# PowerBlock.net
KiCad netlist of a schematic drawn in Altium Designer
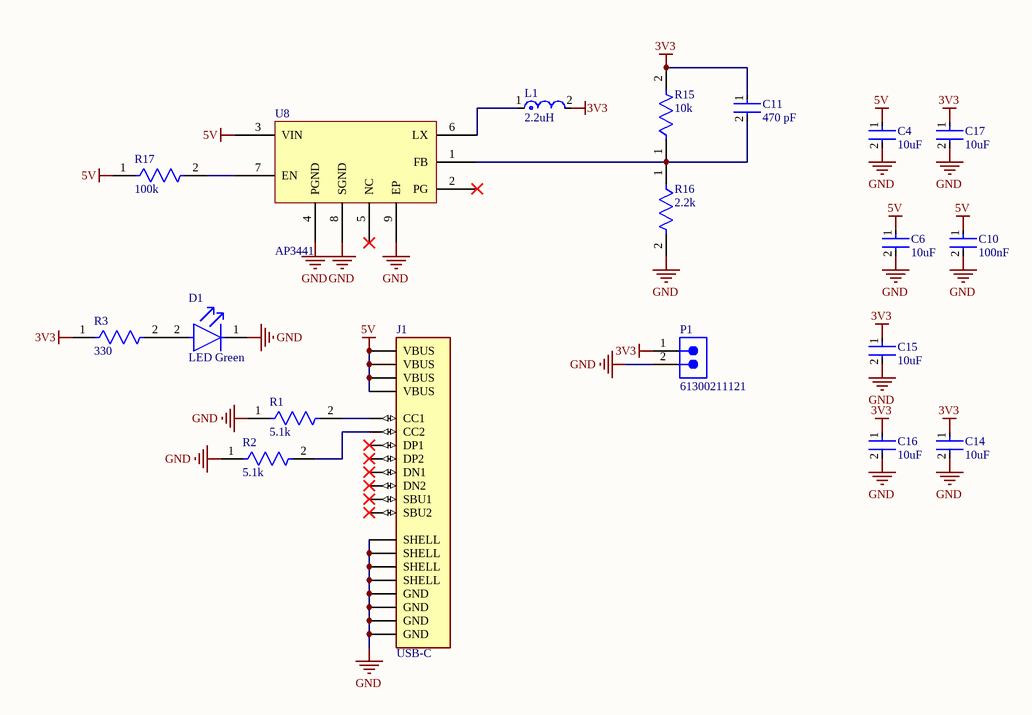
[diagram p0: PowerBlock.SchDoc]

(export (version "E")
  (design (tool "Eeschema 10.0.6"))
  (components
    (comp (ref "C4")
      (value "10uF")
      (footprint "FP-C0805C106K3PACTU-MFG")
      (description "CAP CER 10UF 25V X5R 0805")
      (fields (field (name "TOLERANCE") "10%") (field (name "VOLTAGE") "25V"))
      (libsource (lib "Altium Content Vault") (part "b4654b650e69147ec39a6b967a45e02"))
    )
    (comp (ref "C6")
      (value "10uF")
      (footprint "FP-C0805C106K3PACTU-MFG")
      (description "CAP CER 10UF 25V X5R 0805")
      (fields (field (name "TOLERANCE") "10%") (field (name "VOLTAGE") "25V"))
      (libsource (lib "Altium Content Vault") (part "b4654b650e69147ec39a6b967a45e02"))
    )
    (comp (ref "C10")
      (value "100nF")
      (footprint "FP-C0805C106K3PACTU-MFG")
      (description "CAP CER 10UF 25V X5R 0805")
      (fields (field (name "TOLERANCE") "10%") (field (name "VOLTAGE") "25V"))
      (libsource (lib "Altium Content Vault") (part "b4654b650e69147ec39a6b967a45e02"))
    )
    (comp (ref "C11")
      (value "470 pF")
      (footprint "FP-C0805C106K3PACTU-MFG")
      (description "CAP CER 10UF 25V X5R 0805")
      (fields (field (name "TOLERANCE") "10%") (field (name "VOLTAGE") "25V"))
      (libsource (lib "Altium Content Vault") (part "b4654b650e69147ec39a6b967a45e02"))
    )
    (comp (ref "C14")
      (value "10uF")
      (footprint "FP-C0805C106K3PACTU-MFG")
      (description "CAP CER 10UF 25V X5R 0805")
      (fields (field (name "TOLERANCE") "10%") (field (name "VOLTAGE") "25V"))
      (libsource (lib "Altium Content Vault") (part "b4654b650e69147ec39a6b967a45e02"))
    )
    (comp (ref "C15")
      (value "10uF")
      (footprint "FP-C0805C106K3PACTU-MFG")
      (description "CAP CER 10UF 25V X5R 0805")
      (fields (field (name "TOLERANCE") "10%") (field (name "VOLTAGE") "25V"))
      (libsource (lib "Altium Content Vault") (part "b4654b650e69147ec39a6b967a45e02"))
    )
    (comp (ref "C16")
      (value "10uF")
      (footprint "FP-C0805C106K3PACTU-MFG")
      (description "CAP CER 10UF 25V X5R 0805")
      (fields (field (name "TOLERANCE") "10%") (field (name "VOLTAGE") "25V"))
      (libsource (lib "Altium Content Vault") (part "b4654b650e69147ec39a6b967a45e02"))
    )
    (comp (ref "C17")
      (value "10uF")
      (footprint "FP-C0805C106K3PACTU-MFG")
      (description "CAP CER 10UF 25V X5R 0805")
      (fields (field (name "TOLERANCE") "10%") (field (name "VOLTAGE") "25V"))
      (libsource (lib "Altium Content Vault") (part "b4654b650e69147ec39a6b967a45e02"))
    )
    (comp (ref "D1")
      (value "LED Green")
      (footprint "FP-LTST-C171KGKT-MFG")
      (description "LED GREEN CLEAR SMD")
      (libsource (lib "Altium Content Vault") (part "8706943c75ba83719d021d2fdc84c58"))
    )
    (comp (ref "J1")
      (value "USB-C")
      (footprint "GCT_USB4085-GF-A_REVA4")
      (fields (field (name "MP") "USB4085-GF-A") (field (name "MF") "Global Connector Technology"))
      (libsource (lib "PowerBlock") (part "USB4085-GF-A_REVA4"))
    )
    (comp (ref "L1")
      (value "2.2uH")
      (footprint "FP-XAL4020-MFG")
      (description "Fixed Inductors 2.2uH Shld 20% 5.5A 38.7mOhms AECQ2")
      (fields (field (name "TOLERANCE") "20%"))
      (libsource (lib "Altium Content Vault") (part "4cc4b267dca4c8e51f7102f422741d8"))
    )
    (comp (ref "P1")
      (value "61300211121")
      (footprint "61300211121")
      (description "THT Vertical Pin Header WR-PHD, Pitch 2.54 mm, Single Row, 2 pins")
      (libsource (lib "Altium Content Vault") (part "Header_Male_1R_02P"))
    )
    (comp (ref "R1")
      (value "5.1k")
      (footprint "FP-CRGP0805-IPC_C")
      (description "CRGP 0805 10K 1%")
      (fields (field (name "MANUFACTURER PART NUMBER") "CRGP0805F10K") (field (name "MANUFACTURER") "TE"))
      (libsource (lib "Altium Content Vault") (part "1029c3af85768c4190bb7ad29bc67b5"))
    )
    (comp (ref "R2")
      (value "5.1k")
      (footprint "FP-CRGP0805-IPC_C")
      (description "CRGP 0805 10K 1%")
      (fields (field (name "MANUFACTURER PART NUMBER") "CRGP0805F10K") (field (name "MANUFACTURER") "TE"))
      (libsource (lib "Altium Content Vault") (part "1029c3af85768c4190bb7ad29bc67b5"))
    )
    (comp (ref "R3")
      (value "330")
      (footprint "FP-CRGP0805-IPC_C")
      (description "CRGP 0805 10K 1%")
      (fields (field (name "MANUFACTURER PART NUMBER") "CRGP0805F10K") (field (name "MANUFACTURER") "TE"))
      (libsource (lib "Altium Content Vault") (part "1029c3af85768c4190bb7ad29bc67b5"))
    )
    (comp (ref "R15")
      (value "10k")
      (footprint "FP-CRGP0805-IPC_C")
      (description "CRGP 0805 10K 1%")
      (fields (field (name "MANUFACTURER PART NUMBER") "CRGP0805F10K") (field (name "MANUFACTURER") "TE"))
      (libsource (lib "Altium Content Vault") (part "1029c3af85768c4190bb7ad29bc67b5"))
    )
    (comp (ref "R16")
      (value "2.2k")
      (footprint "FP-CRGP0805-IPC_C")
      (description "CRGP 0805 10K 1%")
      (fields (field (name "MANUFACTURER PART NUMBER") "CRGP0805F10K") (field (name "MANUFACTURER") "TE"))
      (libsource (lib "Altium Content Vault") (part "1029c3af85768c4190bb7ad29bc67b5"))
    )
    (comp (ref "R17")
      (value "100k")
      (footprint "FP-CRGP0805-IPC_C")
      (description "CRGP 0805 10K 1%")
      (fields (field (name "MANUFACTURER PART NUMBER") "CRGP0805F10K") (field (name "MANUFACTURER") "TE"))
      (libsource (lib "Altium Content Vault") (part "1029c3af85768c4190bb7ad29bc67b5"))
    )
    (comp (ref "U8")
      (value "AP3441")
      (footprint "SON50P201X201X60-9M")
      (description "DC-DC Switching Buck Regulator, Adjustable, 2.7 to 5.5 V in, 0.6 to 5.5 V/3 A, U-DFN2020-8")
      (fields
        (field (name "MANUFACTURER") "Diodes Inc.")
        (field (name "MANUFACTURER PART NUMBER") "AP3441LSHE-7B")
      )
      (libsource (lib "PowerBlock") (part "AP3441LSHE-7B"))
    )
  )
  (nets
    (net (code "1") (name "3V3") (class "Default")
      (node (ref "C11") (pin "1") (pinfunction "1_1") (pintype "passive"))
      (node (ref "C14") (pin "1") (pinfunction "1_1") (pintype "passive"))
      (node (ref "C15") (pin "1") (pinfunction "1_1") (pintype "passive"))
      (node (ref "C16") (pin "1") (pinfunction "1_1") (pintype "passive"))
      (node (ref "C17") (pin "1") (pinfunction "1_1") (pintype "passive"))
      (node (ref "L1") (pin "2") (pinfunction "2_2") (pintype "passive"))
      (node (ref "P1") (pin "1") (pinfunction "1_1") (pintype "passive"))
      (node (ref "R15") (pin "2") (pinfunction "2_2") (pintype "passive"))
      (node (ref "R3") (pin "1") (pinfunction "1_1") (pintype "passive"))
    )
    (net (code "2") (name "5V") (class "Default")
      (node (ref "C10") (pin "1") (pinfunction "1_1") (pintype "passive"))
      (node (ref "C4") (pin "1") (pinfunction "1_1") (pintype "passive"))
      (node (ref "C6") (pin "1") (pinfunction "1_1") (pintype "passive"))
      (node (ref "J1") (pin "A4") (pinfunction "VBUS_A4") (pintype "power_in"))
      (node (ref "J1") (pin "A9") (pinfunction "VBUS_A9") (pintype "power_in"))
      (node (ref "J1") (pin "B4") (pinfunction "VBUS_B4") (pintype "power_in"))
      (node (ref "J1") (pin "B9") (pinfunction "VBUS_B9") (pintype "power_in"))
      (node (ref "R17") (pin "1") (pinfunction "1_1") (pintype "passive"))
      (node (ref "U8") (pin "3") (pinfunction "VIN_3") (pintype "power_in"))
    )
    (net (code "3") (name "GND") (class "Default")
      (node (ref "C10") (pin "2") (pinfunction "2_2") (pintype "passive"))
      (node (ref "C14") (pin "2") (pinfunction "2_2") (pintype "passive"))
      (node (ref "C15") (pin "2") (pinfunction "2_2") (pintype "passive"))
      (node (ref "C16") (pin "2") (pinfunction "2_2") (pintype "passive"))
      (node (ref "C17") (pin "2") (pinfunction "2_2") (pintype "passive"))
      (node (ref "C4") (pin "2") (pinfunction "2_2") (pintype "passive"))
      (node (ref "C6") (pin "2") (pinfunction "2_2") (pintype "passive"))
      (node (ref "D1") (pin "1") (pinfunction "C_1") (pintype "passive"))
      (node (ref "J1") (pin "A1") (pinfunction "GND_A1") (pintype "power_in"))
      (node (ref "J1") (pin "A12") (pinfunction "GND_A12") (pintype "power_in"))
      (node (ref "J1") (pin "B1") (pinfunction "GND_B1") (pintype "power_in"))
      (node (ref "J1") (pin "B12") (pinfunction "GND_B12") (pintype "power_in"))
      (node (ref "J1") (pin "S1") (pinfunction "SHELL_S1") (pintype "passive"))
      (node (ref "J1") (pin "S2") (pinfunction "SHELL_S2") (pintype "passive"))
      (node (ref "J1") (pin "S3") (pinfunction "SHELL_S3") (pintype "passive"))
      (node (ref "J1") (pin "S4") (pinfunction "SHELL_S4") (pintype "passive"))
      (node (ref "P1") (pin "2") (pinfunction "2_2") (pintype "passive"))
      (node (ref "R1") (pin "1") (pinfunction "1_1") (pintype "passive"))
      (node (ref "R16") (pin "2") (pinfunction "2_2") (pintype "passive"))
      (node (ref "R2") (pin "1") (pinfunction "1_1") (pintype "passive"))
      (node (ref "U8") (pin "4") (pinfunction "PGND_4") (pintype "power_in"))
      (node (ref "U8") (pin "8") (pinfunction "SGND_8") (pintype "power_in"))
      (node (ref "U8") (pin "9") (pinfunction "EP_9") (pintype "passive"))
    )
    (net (code "4") (name "Net-(D1-A)") (class "Default")
      (node (ref "D1") (pin "2") (pinfunction "A_2") (pintype "passive"))
      (node (ref "R3") (pin "2") (pinfunction "2_2") (pintype "passive"))
    )
    (net (code "5") (name "Net-(J1-CC1)") (class "Default")
      (node (ref "J1") (pin "A5") (pinfunction "CC1_A5") (pintype "bidirectional"))
      (node (ref "R1") (pin "2") (pinfunction "2_2") (pintype "passive"))
    )
    (net (code "6") (name "Net-(J1-CC2)") (class "Default")
      (node (ref "J1") (pin "B5") (pinfunction "CC2_B5") (pintype "bidirectional"))
      (node (ref "R2") (pin "2") (pinfunction "2_2") (pintype "passive"))
    )
    (net (code "7") (name "Net-(U8-EN)") (class "Default")
      (node (ref "R17") (pin "2") (pinfunction "2_2") (pintype "passive"))
      (node (ref "U8") (pin "7") (pinfunction "EN_7") (pintype "passive"))
    )
    (net (code "8") (name "Net-(U8-FB)") (class "Default")
      (node (ref "C11") (pin "2") (pinfunction "2_2") (pintype "passive"))
      (node (ref "R15") (pin "1") (pinfunction "1_1") (pintype "passive"))
      (node (ref "R16") (pin "1") (pinfunction "1_1") (pintype "passive"))
      (node (ref "U8") (pin "1") (pinfunction "FB_1") (pintype "passive"))
    )
    (net (code "9") (name "Net-(U8-LX)") (class "Default")
      (node (ref "L1") (pin "1") (pinfunction "1_1") (pintype "passive"))
      (node (ref "U8") (pin "6") (pinfunction "LX_6") (pintype "passive"))
    )
    (net (code "10") (name "unconnected-(J1-DN1-PadA7)") (class "Default")
      (node (ref "J1") (pin "A7") (pinfunction "DN1_A7") (pintype "bidirectional+no_connect"))
    )
    (net (code "11") (name "unconnected-(J1-DN2-PadB7)") (class "Default")
      (node (ref "J1") (pin "B7") (pinfunction "DN2_B7") (pintype "bidirectional+no_connect"))
    )
    (net (code "12") (name "unconnected-(J1-DP1-PadA6)") (class "Default")
      (node (ref "J1") (pin "A6") (pinfunction "DP1_A6") (pintype "bidirectional+no_connect"))
    )
    (net (code "13") (name "unconnected-(J1-DP2-PadB6)") (class "Default")
      (node (ref "J1") (pin "B6") (pinfunction "DP2_B6") (pintype "bidirectional+no_connect"))
    )
    (net (code "14") (name "unconnected-(J1-SBU1-PadA8)") (class "Default")
      (node (ref "J1") (pin "A8") (pinfunction "SBU1_A8") (pintype "bidirectional+no_connect"))
    )
    (net (code "15") (name "unconnected-(J1-SBU2-PadB8)") (class "Default")
      (node (ref "J1") (pin "B8") (pinfunction "SBU2_B8") (pintype "bidirectional+no_connect"))
    )
    (net (code "16") (name "unconnected-(U8-NC-Pad5)") (class "Default")
      (node (ref "U8") (pin "5") (pinfunction "NC_5") (pintype "power_in+no_connect"))
    )
    (net (code "17") (name "unconnected-(U8-PG-Pad2)") (class "Default")
      (node (ref "U8") (pin "2") (pinfunction "PG_2") (pintype "passive+no_connect"))
    )
  )
)
